# PassElement.net
KiCad netlist of a schematic drawn in Altium Designer
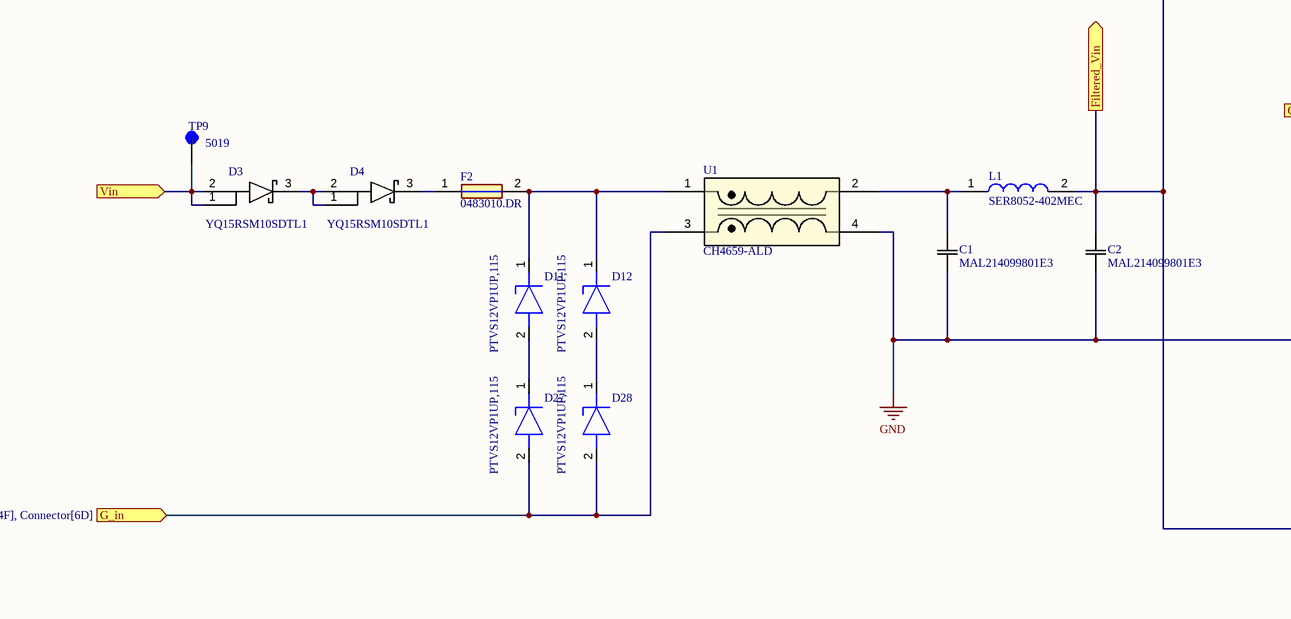
[diagram p0: PassElement.SchDoc, left]
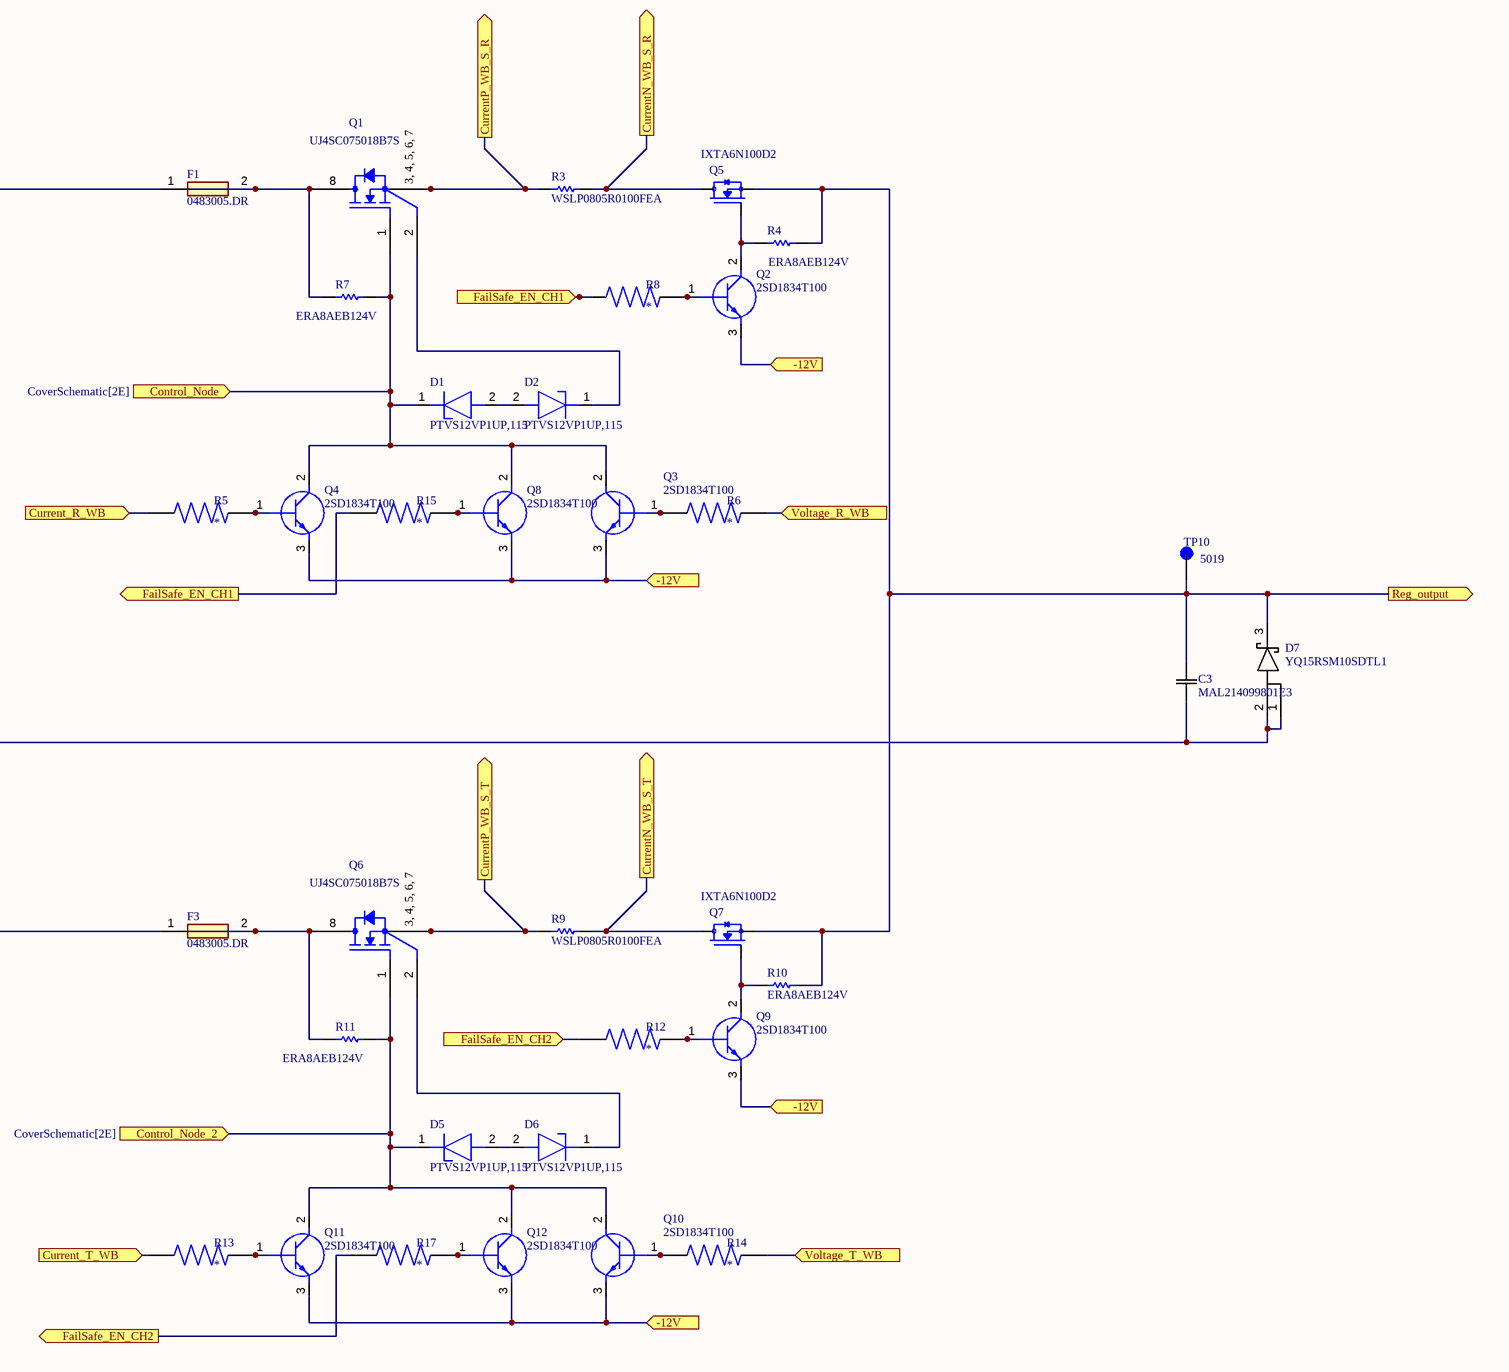
[diagram p1: PassElement.SchDoc, right]

(export (version "E")
  (design (tool "Eeschema 10.0.6"))
  (components
    (comp (ref "C1")
      (value "MAL214099801E3")
      (footprint "CAP_140CRH_1010_VIS")
      (description "No Description Available")
      (libsource (lib "MAL214099801E3") (part "MAL214099801E3"))
    )
    (comp (ref "C2")
      (value "MAL214099801E3")
      (footprint "CAP_140CRH_1010_VIS")
      (description "No Description Available")
      (libsource (lib "MAL214099801E3") (part "MAL214099801E3"))
    )
    (comp (ref "C3")
      (value "MAL214099801E3")
      (footprint "CAP_140CRH_1010_VIS")
      (description "No Description Available")
      (libsource (lib "MAL214099801E3") (part "MAL214099801E3"))
    )
    (comp (ref "D1")
      (value "PTVS12VP1UP,115")
      (footprint "SamacSys:PMEG3050EP115")
      (description "Diode ESD (Uni-directional)")
      (fields (field (name "MOUSER PART NUMBER") "771-PTVS12VP1UP115"))
      (libsource (lib "SamacSys") (part "PTVS12VP1UP,115"))
    )
    (comp (ref "D2")
      (value "PTVS12VP1UP,115")
      (footprint "SamacSys:PMEG3050EP115")
      (description "Diode ESD (Uni-directional)")
      (fields (field (name "MOUSER PART NUMBER") "771-PTVS12VP1UP115"))
      (libsource (lib "SamacSys") (part "PTVS12VP1UP,115"))
    )
    (comp (ref "D3")
      (value "YQ15RSM10SDTL1")
      (footprint "SamacSys:YQ15RSM10SDTL1")
      (description "Schottky Diode")
      (fields (field (name "MOUSER PART NUMBER") "755-YQ15RSM10SDTL1"))
      (libsource (lib "SamacSys") (part "YQ15RSM10SDTL1"))
    )
    (comp (ref "D4")
      (value "YQ15RSM10SDTL1")
      (footprint "SamacSys:YQ15RSM10SDTL1")
      (description "Schottky Diode")
      (fields (field (name "MOUSER PART NUMBER") "755-YQ15RSM10SDTL1"))
      (libsource (lib "SamacSys") (part "YQ15RSM10SDTL1"))
    )
    (comp (ref "D5")
      (value "PTVS12VP1UP,115")
      (footprint "SamacSys:PMEG3050EP115")
      (description "Diode ESD (Uni-directional)")
      (fields (field (name "MOUSER PART NUMBER") "771-PTVS12VP1UP115"))
      (libsource (lib "SamacSys") (part "PTVS12VP1UP,115"))
    )
    (comp (ref "D6")
      (value "PTVS12VP1UP,115")
      (footprint "SamacSys:PMEG3050EP115")
      (description "Diode ESD (Uni-directional)")
      (fields (field (name "MOUSER PART NUMBER") "771-PTVS12VP1UP115"))
      (libsource (lib "SamacSys") (part "PTVS12VP1UP,115"))
    )
    (comp (ref "D7")
      (value "YQ15RSM10SDTL1")
      (footprint "SamacSys:YQ15RSM10SDTL1")
      (description "Schottky Diode")
      (fields (field (name "MOUSER PART NUMBER") "755-YQ15RSM10SDTL1"))
      (libsource (lib "SamacSys") (part "YQ15RSM10SDTL1"))
    )
    (comp (ref "D11")
      (value "PTVS12VP1UP,115")
      (footprint "SamacSys:PMEG3050EP115")
      (description "Diode ESD (Uni-directional)")
      (fields (field (name "MOUSER PART NUMBER") "771-PTVS12VP1UP115"))
      (libsource (lib "SamacSys") (part "PTVS12VP1UP,115"))
    )
    (comp (ref "D12")
      (value "PTVS12VP1UP,115")
      (footprint "SamacSys:PMEG3050EP115")
      (description "Diode ESD (Uni-directional)")
      (fields (field (name "MOUSER PART NUMBER") "771-PTVS12VP1UP115"))
      (libsource (lib "SamacSys") (part "PTVS12VP1UP,115"))
    )
    (comp (ref "D27")
      (value "PTVS12VP1UP,115")
      (footprint "SamacSys:PMEG3050EP115")
      (description "Diode ESD (Uni-directional)")
      (fields (field (name "MOUSER PART NUMBER") "771-PTVS12VP1UP115"))
      (libsource (lib "SamacSys") (part "PTVS12VP1UP,115"))
    )
    (comp (ref "D28")
      (value "PTVS12VP1UP,115")
      (footprint "SamacSys:PMEG3050EP115")
      (description "Diode ESD (Uni-directional)")
      (fields (field (name "MOUSER PART NUMBER") "771-PTVS12VP1UP115"))
      (libsource (lib "SamacSys") (part "PTVS12VP1UP,115"))
    )
    (comp (ref "F1")
      (value "0483005.DR")
      (footprint "SamacSys:FUSC3316X137N")
      (description "Fuse")
      (fields (field (name "MOUSER PART NUMBER") "576-0483005.DR"))
      (libsource (lib "*") (part "0483005.DR"))
    )
    (comp (ref "F2")
      (value "0483010.DR")
      (footprint "SamacSys:FUSC3316X137N")
      (description "Fuse")
      (libsource (lib "*") (part "0483010.DR"))
    )
    (comp (ref "F3")
      (value "0483005.DR")
      (footprint "SamacSys:FUSC3316X137N")
      (description "Fuse")
      (fields (field (name "MOUSER PART NUMBER") "576-0483005.DR"))
      (libsource (lib "*") (part "0483005.DR"))
    )
    (comp (ref "L1")
      (value "SER8052-402MEC")
      (footprint "SamacSys:SER8052402MEC")
      (description "Inductor")
      (fields (field (name "MOUSER PART NUMBER") "994-SER8052-402MEC"))
      (libsource (lib "SamacSys") (part "SER8052-402MEC"))
    )
    (comp (ref "Q1")
      (value "UJ4SC075018B7S")
      (footprint "UJ4SC075018B7S")
      (description "MOSFET 750V/18mO,SICFET,G4,TO263-7")
      (libsource (lib "UJ4SC075018B7S") (part "UJ4SC075018B7S"))
    )
    (comp (ref "Q2")
      (value "2SD1834T100")
      (footprint "SamacSys:RJP020N06")
      (description "Transistor BJT NPN")
      (fields (field (name "MOUSER PART NUMBER") "755-2SD1834T100"))
      (libsource (lib "*") (part "2SD1834T100"))
    )
    (comp (ref "Q3")
      (value "2SD1834T100")
      (footprint "SamacSys:RJP020N06")
      (description "Transistor BJT NPN")
      (fields (field (name "MOUSER PART NUMBER") "755-2SD1834T100"))
      (libsource (lib "*") (part "2SD1834T100"))
    )
    (comp (ref "Q4")
      (value "2SD1834T100")
      (footprint "SamacSys:RJP020N06")
      (description "Transistor BJT NPN")
      (fields (field (name "MOUSER PART NUMBER") "755-2SD1834T100"))
      (libsource (lib "*") (part "2SD1834T100"))
    )
    (comp (ref "Q5")
      (value "IXTA6N100D2")
      (footprint "IXTA6N100D2:DPAK254P1524X483-3N")
      (description "N-Channel 1000 V 6 A 2.2 Ohm SMT Depletion Mode Power Mosfet - D2PAK")
      (fields (field (name "MF") "{'manufacturer': u'IXYS'}"))
      (libsource (lib "*") (part "IXTA6N100D2"))
    )
    (comp (ref "Q6")
      (value "UJ4SC075018B7S")
      (footprint "UJ4SC075018B7S")
      (description "MOSFET 750V/18mO,SICFET,G4,TO263-7")
      (libsource (lib "UJ4SC075018B7S") (part "UJ4SC075018B7S"))
    )
    (comp (ref "Q7")
      (value "IXTA6N100D2")
      (footprint "IXTA6N100D2:DPAK254P1524X483-3N")
      (description "N-Channel 1000 V 6 A 2.2 Ohm SMT Depletion Mode Power Mosfet - D2PAK")
      (fields (field (name "MF") "{'manufacturer': u'IXYS'}"))
      (libsource (lib "*") (part "IXTA6N100D2"))
    )
    (comp (ref "Q8")
      (value "2SD1834T100")
      (footprint "SamacSys:RJP020N06")
      (description "Transistor BJT NPN")
      (fields (field (name "MOUSER PART NUMBER") "755-2SD1834T100"))
      (libsource (lib "*") (part "2SD1834T100"))
    )
    (comp (ref "Q9")
      (value "2SD1834T100")
      (footprint "SamacSys:RJP020N06")
      (description "Transistor BJT NPN")
      (fields (field (name "MOUSER PART NUMBER") "755-2SD1834T100"))
      (libsource (lib "*") (part "2SD1834T100"))
    )
    (comp (ref "Q10")
      (value "2SD1834T100")
      (footprint "SamacSys:RJP020N06")
      (description "Transistor BJT NPN")
      (fields (field (name "MOUSER PART NUMBER") "755-2SD1834T100"))
      (libsource (lib "*") (part "2SD1834T100"))
    )
    (comp (ref "Q11")
      (value "2SD1834T100")
      (footprint "SamacSys:RJP020N06")
      (description "Transistor BJT NPN")
      (fields (field (name "MOUSER PART NUMBER") "755-2SD1834T100"))
      (libsource (lib "*") (part "2SD1834T100"))
    )
    (comp (ref "Q12")
      (value "2SD1834T100")
      (footprint "SamacSys:RJP020N06")
      (description "Transistor BJT NPN")
      (fields (field (name "MOUSER PART NUMBER") "755-2SD1834T100"))
      (libsource (lib "*") (part "2SD1834T100"))
    )
    (comp (ref "R3")
      (value "WSLP0805R0100FEA")
      (footprint "RESC2013X58X38LL25T25")
      (fields (field (name "MANUFACTURER") "Vishay Dale"))
      (libsource (lib "Altium Content Vault") (part "RES"))
    )
    (comp (ref "R4")
      (value "ERA8AEB124V")
      (footprint "RESC3216X70X50LL20T25")
      (fields (field (name "MANUFACTURER") "Panasonic"))
      (libsource (lib "Altium Content Vault") (part "RES"))
    )
    (comp (ref "R5")
      (value "MCT06030C1001FP500")
      (footprint "MCT06030C1001FP500:RESC1508X55N")
      (description "Res Thin Film 0603 1K Ohm 1% 0.1W(1/10W) ?50ppm/C Molded SMD Automotive Medical T/R")
      (fields (field (name "ALTIUM_VALUE") "*") (field (name "MF") "{'manufacturer': u'Vishay Beyschlag'}"))
      (libsource (lib "MCT06030C1001FP500") (part "MCT06030C1001FP500"))
    )
    (comp (ref "R6")
      (value "MCT06030C1001FP500")
      (footprint "MCT06030C1001FP500:RESC1508X55N")
      (description "Res Thin Film 0603 1K Ohm 1% 0.1W(1/10W) ?50ppm/C Molded SMD Automotive Medical T/R")
      (fields (field (name "ALTIUM_VALUE") "*") (field (name "MF") "{'manufacturer': u'Vishay Beyschlag'}"))
      (libsource (lib "MCT06030C1001FP500") (part "MCT06030C1001FP500"))
    )
    (comp (ref "R7")
      (value "ERA8AEB124V")
      (footprint "RESC3216X70X50LL20T25")
      (fields (field (name "MANUFACTURER") "Panasonic"))
      (libsource (lib "Altium Content Vault") (part "RES"))
    )
    (comp (ref "R8")
      (value "MCT06030C1001FP500")
      (footprint "MCT06030C1001FP500:RESC1508X55N")
      (description "Res Thin Film 0603 1K Ohm 1% 0.1W(1/10W) ?50ppm/C Molded SMD Automotive Medical T/R")
      (fields (field (name "ALTIUM_VALUE") "*") (field (name "MF") "{'manufacturer': u'Vishay Beyschlag'}"))
      (libsource (lib "MCT06030C1001FP500") (part "MCT06030C1001FP500"))
    )
    (comp (ref "R9")
      (value "WSLP0805R0100FEA")
      (footprint "RESC2013X58X38LL25T25")
      (fields (field (name "MANUFACTURER") "Vishay Dale"))
      (libsource (lib "Altium Content Vault") (part "RES"))
    )
    (comp (ref "R10")
      (value "ERA8AEB124V")
      (footprint "RESC3216X70X50LL20T25")
      (fields (field (name "MANUFACTURER") "Panasonic"))
      (libsource (lib "Altium Content Vault") (part "RES"))
    )
    (comp (ref "R11")
      (value "ERA8AEB124V")
      (footprint "RESC3216X70X50LL20T25")
      (fields (field (name "MANUFACTURER") "Panasonic"))
      (libsource (lib "Altium Content Vault") (part "RES"))
    )
    (comp (ref "R12")
      (value "MCT06030C1001FP500")
      (footprint "MCT06030C1001FP500:RESC1508X55N")
      (description "Res Thin Film 0603 1K Ohm 1% 0.1W(1/10W) ?50ppm/C Molded SMD Automotive Medical T/R")
      (fields (field (name "ALTIUM_VALUE") "*") (field (name "MF") "{'manufacturer': u'Vishay Beyschlag'}"))
      (libsource (lib "MCT06030C1001FP500") (part "MCT06030C1001FP500"))
    )
    (comp (ref "R13")
      (value "MCT06030C1001FP500")
      (footprint "MCT06030C1001FP500:RESC1508X55N")
      (description "Res Thin Film 0603 1K Ohm 1% 0.1W(1/10W) ?50ppm/C Molded SMD Automotive Medical T/R")
      (fields (field (name "ALTIUM_VALUE") "*") (field (name "MF") "{'manufacturer': u'Vishay Beyschlag'}"))
      (libsource (lib "MCT06030C1001FP500") (part "MCT06030C1001FP500"))
    )
    (comp (ref "R14")
      (value "MCT06030C1001FP500")
      (footprint "MCT06030C1001FP500:RESC1508X55N")
      (description "Res Thin Film 0603 1K Ohm 1% 0.1W(1/10W) ?50ppm/C Molded SMD Automotive Medical T/R")
      (fields (field (name "ALTIUM_VALUE") "*") (field (name "MF") "{'manufacturer': u'Vishay Beyschlag'}"))
      (libsource (lib "MCT06030C1001FP500") (part "MCT06030C1001FP500"))
    )
    (comp (ref "R15")
      (value "MCT06030C1001FP500")
      (footprint "MCT06030C1001FP500:RESC1508X55N")
      (description "Res Thin Film 0603 1K Ohm 1% 0.1W(1/10W) ?50ppm/C Molded SMD Automotive Medical T/R")
      (fields (field (name "ALTIUM_VALUE") "*") (field (name "MF") "{'manufacturer': u'Vishay Beyschlag'}"))
      (libsource (lib "MCT06030C1001FP500") (part "MCT06030C1001FP500"))
    )
    (comp (ref "R17")
      (value "MCT06030C1001FP500")
      (footprint "MCT06030C1001FP500:RESC1508X55N")
      (description "Res Thin Film 0603 1K Ohm 1% 0.1W(1/10W) ?50ppm/C Molded SMD Automotive Medical T/R")
      (fields (field (name "ALTIUM_VALUE") "*") (field (name "MF") "{'manufacturer': u'Vishay Beyschlag'}"))
      (libsource (lib "MCT06030C1001FP500") (part "MCT06030C1001FP500"))
    )
    (comp (ref "TP9")
      (value "5019")
      (footprint "5019:KEYSTONE_5019")
      (fields (field (name "MF") "{'manufacturer': u'Keystone Electronics'}"))
      (libsource (lib "*") (part "5019"))
    )
    (comp (ref "TP10")
      (value "5019")
      (footprint "5019:KEYSTONE_5019")
      (fields (field (name "MF") "{'manufacturer': u'Keystone Electronics'}"))
      (libsource (lib "*") (part "5019"))
    )
    (comp (ref "U1")
      (value "CH4659-ALD")
      (footprint "CH4659-ALD_COC")
      (description "No Description Available")
      (libsource (lib "CH4659-ALD") (part "CH4659-ALD"))
    )
  )
  (nets
    (net (code "1") (name "/-12V") (class "Default")
      (node (ref "Q10") (pin "3") (pinfunction "E_3") (pintype "passive"))
      (node (ref "Q11") (pin "3") (pinfunction "E_3") (pintype "passive"))
      (node (ref "Q12") (pin "3") (pinfunction "E_3") (pintype "passive"))
      (node (ref "Q2") (pin "3") (pinfunction "E_3") (pintype "passive"))
      (node (ref "Q3") (pin "3") (pinfunction "E_3") (pintype "passive"))
      (node (ref "Q4") (pin "3") (pinfunction "E_3") (pintype "passive"))
      (node (ref "Q8") (pin "3") (pinfunction "E_3") (pintype "passive"))
      (node (ref "Q9") (pin "3") (pinfunction "E_3") (pintype "passive"))
    )
    (net (code "2") (name "/Control_Node") (class "Default")
      (node (ref "D1") (pin "1") (pinfunction "K_1") (pintype "passive"))
      (node (ref "Q1") (pin "1") (pinfunction "1_1") (pintype "passive"))
      (node (ref "Q3") (pin "2") (pinfunction "C_2") (pintype "passive"))
      (node (ref "Q4") (pin "2") (pinfunction "C_2") (pintype "passive"))
      (node (ref "Q8") (pin "2") (pinfunction "C_2") (pintype "passive"))
      (node (ref "R7") (pin "2") (pinfunction "2_2") (pintype "passive"))
    )
    (net (code "3") (name "/Control_Node_2") (class "Default")
      (node (ref "D5") (pin "1") (pinfunction "K_1") (pintype "passive"))
      (node (ref "Q10") (pin "2") (pinfunction "C_2") (pintype "passive"))
      (node (ref "Q11") (pin "2") (pinfunction "C_2") (pintype "passive"))
      (node (ref "Q12") (pin "2") (pinfunction "C_2") (pintype "passive"))
      (node (ref "Q6") (pin "1") (pinfunction "1_1") (pintype "passive"))
      (node (ref "R11") (pin "2") (pinfunction "2_2") (pintype "passive"))
    )
    (net (code "4") (name "/CurrentN_WB_S_R") (class "Default")
      (node (ref "Q5") (pin "4") (pinfunction "D_4") (pintype "passive"))
      (node (ref "R3") (pin "2") (pinfunction "2_2") (pintype "passive"))
    )
    (net (code "5") (name "/CurrentN_WB_S_T") (class "Default")
      (node (ref "Q7") (pin "4") (pinfunction "D_4") (pintype "passive"))
      (node (ref "R9") (pin "2") (pinfunction "2_2") (pintype "passive"))
    )
    (net (code "6") (name "/CurrentP_WB_S_R") (class "Default")
      (node (ref "Q1") (pin "3") (pinfunction "3_3") (pintype "passive"))
      (node (ref "Q1") (pin "4") (pinfunction "4_4") (pintype "passive"))
      (node (ref "Q1") (pin "5") (pinfunction "5_5") (pintype "passive"))
      (node (ref "Q1") (pin "6") (pinfunction "6_6") (pintype "passive"))
      (node (ref "Q1") (pin "7") (pinfunction "7_7") (pintype "passive"))
      (node (ref "R3") (pin "1") (pinfunction "1_1") (pintype "passive"))
    )
    (net (code "7") (name "/CurrentP_WB_S_T") (class "Default")
      (node (ref "Q6") (pin "3") (pinfunction "3_3") (pintype "passive"))
      (node (ref "Q6") (pin "4") (pinfunction "4_4") (pintype "passive"))
      (node (ref "Q6") (pin "5") (pinfunction "5_5") (pintype "passive"))
      (node (ref "Q6") (pin "6") (pinfunction "6_6") (pintype "passive"))
      (node (ref "Q6") (pin "7") (pinfunction "7_7") (pintype "passive"))
      (node (ref "R9") (pin "1") (pinfunction "1_1") (pintype "passive"))
    )
    (net (code "8") (name "/Current_R_WB") (class "Default")
      (node (ref "R5") (pin "1") (pinfunction "1_1") (pintype "passive"))
    )
    (net (code "9") (name "/Current_T_WB") (class "Default")
      (node (ref "R13") (pin "1") (pinfunction "1_1") (pintype "passive"))
    )
    (net (code "10") (name "/FailSafe_EN_CH1") (class "Default")
      (node (ref "R15") (pin "1") (pinfunction "1_1") (pintype "passive"))
      (node (ref "R8") (pin "1") (pinfunction "1_1") (pintype "passive"))
    )
    (net (code "11") (name "/FailSafe_EN_CH2") (class "Default")
      (node (ref "R12") (pin "1") (pinfunction "1_1") (pintype "passive"))
      (node (ref "R17") (pin "1") (pinfunction "1_1") (pintype "passive"))
    )
    (net (code "12") (name "/Filtered_Vin") (class "Default")
      (node (ref "C2") (pin "2") (pinfunction "2_2") (pintype "passive"))
      (node (ref "F1") (pin "1") (pinfunction "1_1") (pintype "passive"))
      (node (ref "F3") (pin "1") (pinfunction "1_1") (pintype "passive"))
      (node (ref "L1") (pin "2") (pinfunction "2_2") (pintype "passive"))
    )
    (net (code "13") (name "/G_in") (class "Default")
      (node (ref "D27") (pin "2") (pinfunction "A_2") (pintype "passive"))
      (node (ref "D28") (pin "2") (pinfunction "A_2") (pintype "passive"))
      (node (ref "U1") (pin "3") (pinfunction "3_3") (pintype "passive"))
    )
    (net (code "14") (name "/Reg_output") (class "Default")
      (node (ref "C3") (pin "2") (pinfunction "2_2") (pintype "passive"))
      (node (ref "D7") (pin "3") (pinfunction "K_3") (pintype "passive"))
      (node (ref "Q5") (pin "3") (pinfunction "S_3") (pintype "passive"))
      (node (ref "Q7") (pin "3") (pinfunction "S_3") (pintype "passive"))
      (node (ref "R10") (pin "2") (pinfunction "2_2") (pintype "passive"))
      (node (ref "R4") (pin "2") (pinfunction "2_2") (pintype "passive"))
      (node (ref "TP10") (pin "TP") (pinfunction "TP_TP") (pintype "passive"))
    )
    (net (code "15") (name "/Vin") (class "Default")
      (node (ref "D3") (pin "1") (pinfunction "A1_1") (pintype "passive"))
      (node (ref "D3") (pin "2") (pinfunction "A2_2") (pintype "passive"))
      (node (ref "TP9") (pin "TP") (pinfunction "TP_TP") (pintype "passive"))
    )
    (net (code "16") (name "/Voltage_R_WB") (class "Default")
      (node (ref "R6") (pin "2") (pinfunction "2_2") (pintype "passive"))
    )
    (net (code "17") (name "/Voltage_T_WB") (class "Default")
      (node (ref "R14") (pin "2") (pinfunction "2_2") (pintype "passive"))
    )
    (net (code "18") (name "GND") (class "Default")
      (node (ref "C1") (pin "1") (pinfunction "1_1") (pintype "passive"))
      (node (ref "C2") (pin "1") (pinfunction "1_1") (pintype "passive"))
      (node (ref "C3") (pin "1") (pinfunction "1_1") (pintype "passive"))
      (node (ref "D7") (pin "1") (pinfunction "A1_1") (pintype "passive"))
      (node (ref "D7") (pin "2") (pinfunction "A2_2") (pintype "passive"))
      (node (ref "U1") (pin "4") (pinfunction "4_4") (pintype "passive"))
    )
    (net (code "19") (name "Net-(C1-Pad2)") (class "Default")
      (node (ref "C1") (pin "2") (pinfunction "2_2") (pintype "passive"))
      (node (ref "L1") (pin "1") (pinfunction "1_1") (pintype "passive"))
      (node (ref "U1") (pin "2") (pinfunction "2_2") (pintype "passive"))
    )
    (net (code "20") (name "Net-(D1-A)") (class "Default")
      (node (ref "D1") (pin "2") (pinfunction "A_2") (pintype "passive"))
      (node (ref "D2") (pin "2") (pinfunction "A_2") (pintype "passive"))
    )
    (net (code "21") (name "Net-(D2-K)") (class "Default")
      (node (ref "D2") (pin "1") (pinfunction "K_1") (pintype "passive"))
      (node (ref "Q1") (pin "2") (pinfunction "2_2") (pintype "passive"))
    )
    (net (code "22") (name "Net-(D3-K)") (class "Default")
      (node (ref "D3") (pin "3") (pinfunction "K_3") (pintype "passive"))
      (node (ref "D4") (pin "1") (pinfunction "A1_1") (pintype "passive"))
      (node (ref "D4") (pin "2") (pinfunction "A2_2") (pintype "passive"))
    )
    (net (code "23") (name "Net-(D4-K)") (class "Default")
      (node (ref "D4") (pin "3") (pinfunction "K_3") (pintype "passive"))
      (node (ref "F2") (pin "1") (pinfunction "1_1") (pintype "passive"))
    )
    (net (code "24") (name "Net-(D5-A)") (class "Default")
      (node (ref "D5") (pin "2") (pinfunction "A_2") (pintype "passive"))
      (node (ref "D6") (pin "2") (pinfunction "A_2") (pintype "passive"))
    )
    (net (code "25") (name "Net-(D6-K)") (class "Default")
      (node (ref "D6") (pin "1") (pinfunction "K_1") (pintype "passive"))
      (node (ref "Q6") (pin "2") (pinfunction "2_2") (pintype "passive"))
    )
    (net (code "26") (name "Net-(D11-A)") (class "Default")
      (node (ref "D11") (pin "2") (pinfunction "A_2") (pintype "passive"))
      (node (ref "D27") (pin "1") (pinfunction "K_1") (pintype "passive"))
    )
    (net (code "27") (name "Net-(D11-K)") (class "Default")
      (node (ref "D11") (pin "1") (pinfunction "K_1") (pintype "passive"))
      (node (ref "D12") (pin "1") (pinfunction "K_1") (pintype "passive"))
      (node (ref "F2") (pin "2") (pinfunction "2_2") (pintype "passive"))
      (node (ref "U1") (pin "1") (pinfunction "1_1") (pintype "passive"))
    )
    (net (code "28") (name "Net-(D12-A)") (class "Default")
      (node (ref "D12") (pin "2") (pinfunction "A_2") (pintype "passive"))
      (node (ref "D28") (pin "1") (pinfunction "K_1") (pintype "passive"))
    )
    (net (code "29") (name "Net-(F1-Pad2)") (class "Default")
      (node (ref "F1") (pin "2") (pinfunction "2_2") (pintype "passive"))
      (node (ref "Q1") (pin "8") (pinfunction "8_8") (pintype "passive"))
      (node (ref "R7") (pin "1") (pinfunction "1_1") (pintype "passive"))
    )
    (net (code "30") (name "Net-(F3-Pad2)") (class "Default")
      (node (ref "F3") (pin "2") (pinfunction "2_2") (pintype "passive"))
      (node (ref "Q6") (pin "8") (pinfunction "8_8") (pintype "passive"))
      (node (ref "R11") (pin "1") (pinfunction "1_1") (pintype "passive"))
    )
    (net (code "31") (name "Net-(Q2-B)") (class "Default")
      (node (ref "Q2") (pin "1") (pinfunction "B_1") (pintype "passive"))
      (node (ref "R8") (pin "2") (pinfunction "2_2") (pintype "passive"))
    )
    (net (code "32") (name "Net-(Q2-C)") (class "Default")
      (node (ref "Q2") (pin "2") (pinfunction "C_2") (pintype "passive"))
      (node (ref "Q5") (pin "1") (pinfunction "G_1") (pintype "passive"))
      (node (ref "R4") (pin "1") (pinfunction "1_1") (pintype "passive"))
    )
    (net (code "33") (name "Net-(Q3-B)") (class "Default")
      (node (ref "Q3") (pin "1") (pinfunction "B_1") (pintype "passive"))
      (node (ref "R6") (pin "1") (pinfunction "1_1") (pintype "passive"))
    )
    (net (code "34") (name "Net-(Q4-B)") (class "Default")
      (node (ref "Q4") (pin "1") (pinfunction "B_1") (pintype "passive"))
      (node (ref "R5") (pin "2") (pinfunction "2_2") (pintype "passive"))
    )
    (net (code "35") (name "Net-(Q7-G)") (class "Default")
      (node (ref "Q7") (pin "1") (pinfunction "G_1") (pintype "passive"))
      (node (ref "Q9") (pin "2") (pinfunction "C_2") (pintype "passive"))
      (node (ref "R10") (pin "1") (pinfunction "1_1") (pintype "passive"))
    )
    (net (code "36") (name "Net-(Q8-B)") (class "Default")
      (node (ref "Q8") (pin "1") (pinfunction "B_1") (pintype "passive"))
      (node (ref "R15") (pin "2") (pinfunction "2_2") (pintype "passive"))
    )
    (net (code "37") (name "Net-(Q9-B)") (class "Default")
      (node (ref "Q9") (pin "1") (pinfunction "B_1") (pintype "passive"))
      (node (ref "R12") (pin "2") (pinfunction "2_2") (pintype "passive"))
    )
    (net (code "38") (name "Net-(Q10-B)") (class "Default")
      (node (ref "Q10") (pin "1") (pinfunction "B_1") (pintype "passive"))
      (node (ref "R14") (pin "1") (pinfunction "1_1") (pintype "passive"))
    )
    (net (code "39") (name "Net-(Q11-B)") (class "Default")
      (node (ref "Q11") (pin "1") (pinfunction "B_1") (pintype "passive"))
      (node (ref "R13") (pin "2") (pinfunction "2_2") (pintype "passive"))
    )
    (net (code "40") (name "Net-(Q12-B)") (class "Default")
      (node (ref "Q12") (pin "1") (pinfunction "B_1") (pintype "passive"))
      (node (ref "R17") (pin "2") (pinfunction "2_2") (pintype "passive"))
    )
    (net (code "41") (name "unconnected-(L1-Pad3)") (class "Default")
      (node (ref "L1") (pin "3") (pinfunction "3_3") (pintype "passive"))
    )
  )
)
